# RGB_i2c_v1plusRTC_TH.net
KiCad netlist of a schematic drawn in EAGLE
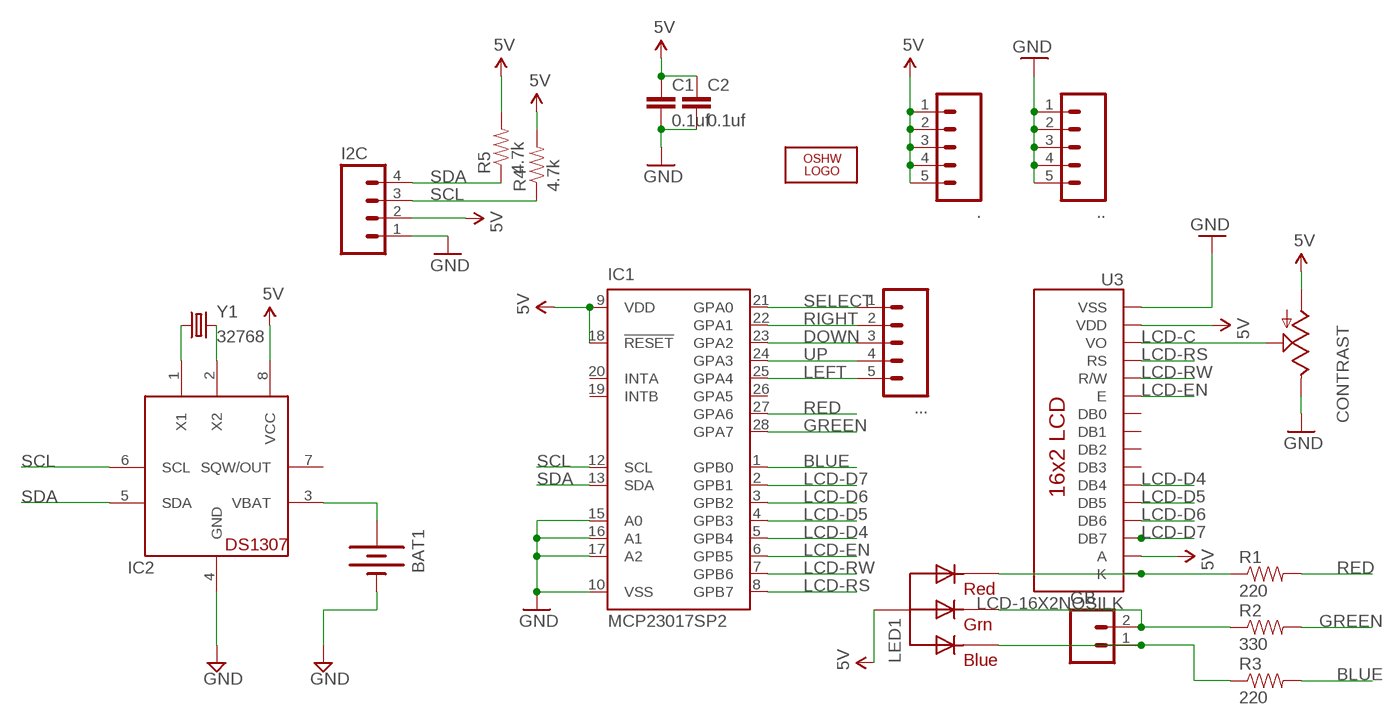
[diagram p0: schematic, sheet 1]

(export (version "E")
  (design (tool "Eeschema 10.0.6"))
  (components
    (comp (ref ".")
      (value "M05LOCK")
      (footprint "eagle-import:1X05_LOCK")
      (libsource (lib "eagle-import") (part "M05LOCK"))
    )
    (comp (ref "..")
      (value "M05LOCK")
      (footprint "eagle-import:1X05_LOCK")
      (libsource (lib "eagle-import") (part "M05LOCK"))
    )
    (comp (ref "...")
      (value "M05LOCK")
      (footprint "eagle-import:1X05_LOCK")
      (libsource (lib "eagle-import") (part "M05LOCK"))
    )
    (comp (ref "BAT1")
      (value "BATTERY12MM")
      (footprint "eagle-import:BATTCON_12MM")
      (libsource (lib "eagle-import") (part "BATTERY12MM"))
    )
    (comp (ref "C1")
      (value "0.1uf")
      (footprint "eagle-import:CAP-PTH-SMALL-KIT")
      (libsource (lib "eagle-import") (part "CAPKIT"))
    )
    (comp (ref "C2")
      (value "0.1uf")
      (footprint "eagle-import:CAP-PTH-SMALL-KIT")
      (libsource (lib "eagle-import") (part "CAPKIT"))
    )
    (comp (ref "CONTRAST")
      (value "TRIM")
      (footprint "eagle-import:6MM")
      (libsource (lib "eagle-import") (part "TRIM"))
    )
    (comp (ref "GB")
      (value "M02LOCK")
      (footprint "eagle-import:1X02_LOCK")
      (libsource (lib "eagle-import") (part "M02LOCK"))
    )
    (comp (ref "I2C")
      (value "M04LOCK")
      (footprint "eagle-import:1X04_LOCK")
      (libsource (lib "eagle-import") (part "M04LOCK"))
    )
    (comp (ref "IC1")
      (value "MCP23017SP2")
      (footprint "eagle-import:DIL28-3-ROUND")
      (libsource (lib "eagle-import") (part "MCP23017SP2"))
    )
    (comp (ref "IC2")
      (value "DS1307")
      (footprint "eagle-import:DIL08")
      (libsource (lib "eagle-import") (part "DS1307"))
    )
    (comp (ref "LED1")
      (value "RGBLED_CA-5MM")
      (footprint "eagle-import:LED5MMRGB")
      (libsource (lib "eagle-import") (part "RGBLED_CA-5MM"))
    )
    (comp (ref "LOGO2")
      (value "OSHW_LOGO_10MILX0350-NT")
      (footprint "eagle-import:OSHW_10X350_NOTEXT")
      (libsource (lib "eagle-import") (part "OSHW_LOGO_10MILX0350-NT"))
    )
    (comp (ref "R1")
      (value "220")
      (footprint "eagle-import:AXIAL-0.3")
      (libsource (lib "eagle-import") (part "RESISTORAXIAL-0.3"))
    )
    (comp (ref "R2")
      (value "330")
      (footprint "eagle-import:AXIAL-0.3")
      (libsource (lib "eagle-import") (part "RESISTORAXIAL-0.3"))
    )
    (comp (ref "R3")
      (value "220")
      (footprint "eagle-import:AXIAL-0.3")
      (libsource (lib "eagle-import") (part "RESISTORAXIAL-0.3"))
    )
    (comp (ref "R4")
      (value "4.7k")
      (footprint "eagle-import:AXIAL-0.3")
      (libsource (lib "eagle-import") (part "RESISTORAXIAL-0.3"))
    )
    (comp (ref "R5")
      (value "4.7k")
      (footprint "eagle-import:AXIAL-0.3")
      (libsource (lib "eagle-import") (part "RESISTORAXIAL-0.3"))
    )
    (comp (ref "U3")
      (value "LCD-16X2NOSILK")
      (footprint "eagle-import:LCD-16X2_NOSILK")
      (libsource (lib "eagle-import") (part "LCD-16X2NOSILK"))
    )
    (comp (ref "Y1")
      (value "32768")
      (footprint "eagle-import:TC38H")
      (libsource (lib "eagle-import") (part "CRYSTALTC38H"))
    )
  )
  (nets
    (net (code "1") (name "/BLUE") (class "Default")
      (node (ref "IC1") (pin "1") (pinfunction "GPB0_1") (pintype "bidirectional"))
      (node (ref "R3") (pin "P$2") (pinfunction "2_P$2") (pintype "passive"))
    )
    (net (code "2") (name "/DOWN") (class "Default")
      (node (ref "...") (pin "3") (pinfunction "3_3") (pintype "passive"))
      (node (ref "IC1") (pin "23") (pinfunction "GPA2_23") (pintype "bidirectional"))
    )
    (net (code "3") (name "/GREEN") (class "Default")
      (node (ref "IC1") (pin "28") (pinfunction "GPA7_28") (pintype "bidirectional"))
      (node (ref "R2") (pin "P$2") (pinfunction "2_P$2") (pintype "passive"))
    )
    (net (code "4") (name "/LCD-C") (class "Default")
      (node (ref "CONTRAST") (pin "S") (pinfunction "S_S") (pintype "passive"))
      (node (ref "U3") (pin "3") (pinfunction "VO_3") (pintype "bidirectional"))
    )
    (net (code "5") (name "/LCD-D4") (class "Default")
      (node (ref "IC1") (pin "5") (pinfunction "GPB4_5") (pintype "bidirectional"))
      (node (ref "U3") (pin "11") (pinfunction "DB4_11") (pintype "bidirectional"))
    )
    (net (code "6") (name "/LCD-D5") (class "Default")
      (node (ref "IC1") (pin "4") (pinfunction "GPB3_4") (pintype "bidirectional"))
      (node (ref "U3") (pin "12") (pinfunction "DB5_12") (pintype "bidirectional"))
    )
    (net (code "7") (name "/LCD-D6") (class "Default")
      (node (ref "IC1") (pin "3") (pinfunction "GPB2_3") (pintype "bidirectional"))
      (node (ref "U3") (pin "13") (pinfunction "DB6_13") (pintype "bidirectional"))
    )
    (net (code "8") (name "/LCD-D7") (class "Default")
      (node (ref "IC1") (pin "2") (pinfunction "GPB1_2") (pintype "bidirectional"))
      (node (ref "U3") (pin "14") (pinfunction "DB7_14") (pintype "bidirectional"))
    )
    (net (code "9") (name "/LCD-EN") (class "Default")
      (node (ref "IC1") (pin "6") (pinfunction "GPB5_6") (pintype "bidirectional"))
      (node (ref "U3") (pin "6") (pinfunction "E_6") (pintype "input"))
    )
    (net (code "10") (name "/LCD-RS") (class "Default")
      (node (ref "IC1") (pin "8") (pinfunction "GPB7_8") (pintype "bidirectional"))
      (node (ref "U3") (pin "4") (pinfunction "RS_4") (pintype "input"))
    )
    (net (code "11") (name "/LCD-RW") (class "Default")
      (node (ref "IC1") (pin "7") (pinfunction "GPB6_7") (pintype "bidirectional"))
      (node (ref "U3") (pin "5") (pinfunction "R/W_5") (pintype "input"))
    )
    (net (code "12") (name "/LEFT") (class "Default")
      (node (ref "...") (pin "5") (pinfunction "5_5") (pintype "passive"))
      (node (ref "IC1") (pin "25") (pinfunction "GPA4_25") (pintype "bidirectional"))
    )
    (net (code "13") (name "/RED") (class "Default")
      (node (ref "IC1") (pin "27") (pinfunction "GPA6_27") (pintype "bidirectional"))
      (node (ref "R1") (pin "P$2") (pinfunction "2_P$2") (pintype "passive"))
    )
    (net (code "14") (name "/RIGHT") (class "Default")
      (node (ref "...") (pin "2") (pinfunction "2_2") (pintype "passive"))
      (node (ref "IC1") (pin "22") (pinfunction "GPA1_22") (pintype "bidirectional"))
    )
    (net (code "15") (name "/SCL") (class "Default")
      (node (ref "I2C") (pin "3") (pinfunction "3_3") (pintype "passive"))
      (node (ref "IC1") (pin "12") (pinfunction "SCL_12") (pintype "input"))
      (node (ref "IC2") (pin "6") (pinfunction "SCL_6") (pintype "bidirectional"))
      (node (ref "R4") (pin "P$1") (pinfunction "1_P$1") (pintype "passive"))
    )
    (net (code "16") (name "/SDA") (class "Default")
      (node (ref "I2C") (pin "4") (pinfunction "4_4") (pintype "passive"))
      (node (ref "IC1") (pin "13") (pinfunction "SDA_13") (pintype "bidirectional"))
      (node (ref "IC2") (pin "5") (pinfunction "SDA_5") (pintype "bidirectional"))
      (node (ref "R5") (pin "P$1") (pinfunction "1_P$1") (pintype "passive"))
    )
    (net (code "17") (name "/SELECT") (class "Default")
      (node (ref "...") (pin "1") (pinfunction "1_1") (pintype "passive"))
      (node (ref "IC1") (pin "21") (pinfunction "GPA0_21") (pintype "bidirectional"))
    )
    (net (code "18") (name "/UP") (class "Default")
      (node (ref "...") (pin "4") (pinfunction "4_4") (pintype "passive"))
      (node (ref "IC1") (pin "24") (pinfunction "GPA3_24") (pintype "bidirectional"))
    )
    (net (code "19") (name "5V") (class "Default")
      (node (ref ".") (pin "1") (pinfunction "1_1") (pintype "passive"))
      (node (ref ".") (pin "2") (pinfunction "2_2") (pintype "passive"))
      (node (ref ".") (pin "3") (pinfunction "3_3") (pintype "passive"))
      (node (ref ".") (pin "4") (pinfunction "4_4") (pintype "passive"))
      (node (ref ".") (pin "5") (pinfunction "5_5") (pintype "passive"))
      (node (ref "C1") (pin "1") (pinfunction "1_1") (pintype "passive"))
      (node (ref "C2") (pin "1") (pinfunction "1_1") (pintype "passive"))
      (node (ref "CONTRAST") (pin "A") (pinfunction "A_A") (pintype "passive"))
      (node (ref "I2C") (pin "2") (pinfunction "2_2") (pintype "passive"))
      (node (ref "IC1") (pin "18") (pinfunction "~{RESET}_18") (pintype "input"))
      (node (ref "IC1") (pin "9") (pinfunction "VDD_9") (pintype "power_in"))
      (node (ref "IC2") (pin "8") (pinfunction "VCC_8") (pintype "power_in"))
      (node (ref "LED1") (pin "2") (pinfunction "VCC_2") (pintype "bidirectional"))
      (node (ref "R4") (pin "P$2") (pinfunction "2_P$2") (pintype "passive"))
      (node (ref "R5") (pin "P$2") (pinfunction "2_P$2") (pintype "passive"))
      (node (ref "U3") (pin "15") (pinfunction "A_15") (pintype "power_in"))
      (node (ref "U3") (pin "2") (pinfunction "VDD_2") (pintype "power_in"))
    )
    (net (code "20") (name "GND") (class "Default")
      (node (ref "..") (pin "1") (pinfunction "1_1") (pintype "passive"))
      (node (ref "..") (pin "2") (pinfunction "2_2") (pintype "passive"))
      (node (ref "..") (pin "3") (pinfunction "3_3") (pintype "passive"))
      (node (ref "..") (pin "4") (pinfunction "4_4") (pintype "passive"))
      (node (ref "..") (pin "5") (pinfunction "5_5") (pintype "passive"))
      (node (ref "BAT1") (pin "GND") (pinfunction "-_GND") (pintype "power_in"))
      (node (ref "C1") (pin "2") (pinfunction "2_2") (pintype "passive"))
      (node (ref "C2") (pin "2") (pinfunction "2_2") (pintype "passive"))
      (node (ref "CONTRAST") (pin "E") (pinfunction "E_E") (pintype "passive"))
      (node (ref "I2C") (pin "1") (pinfunction "1_1") (pintype "passive"))
      (node (ref "IC1") (pin "10") (pinfunction "VSS_10") (pintype "power_in"))
      (node (ref "IC1") (pin "15") (pinfunction "A0_15") (pintype "input"))
      (node (ref "IC1") (pin "16") (pinfunction "A1_16") (pintype "input"))
      (node (ref "IC1") (pin "17") (pinfunction "A2_17") (pintype "input"))
      (node (ref "IC2") (pin "4") (pinfunction "GND_4") (pintype "power_in"))
      (node (ref "U3") (pin "1") (pinfunction "VSS_1") (pintype "power_in"))
    )
    (net (code "21") (name "Net-(BAT1-+)") (class "Default")
      (node (ref "BAT1") (pin "PWR@1") (pinfunction "+_PWR@1") (pintype "power_in"))
      (node (ref "IC2") (pin "3") (pinfunction "VBAT_3") (pintype "power_in"))
    )
    (net (code "22") (name "Net-(IC2-X1)") (class "Default")
      (node (ref "IC2") (pin "1") (pinfunction "X1_1") (pintype "passive"))
      (node (ref "Y1") (pin "1") (pinfunction "1_1") (pintype "passive"))
    )
    (net (code "23") (name "Net-(IC2-X2)") (class "Default")
      (node (ref "IC2") (pin "2") (pinfunction "X2_2") (pintype "passive"))
      (node (ref "Y1") (pin "2") (pinfunction "2_2") (pintype "passive"))
    )
    (net (code "24") (name "Net-(LED1-BLUE)") (class "Default")
      (node (ref "GB") (pin "1") (pinfunction "1_1") (pintype "passive"))
      (node (ref "LED1") (pin "4") (pinfunction "BLUE_4") (pintype "bidirectional"))
      (node (ref "R3") (pin "P$1") (pinfunction "1_P$1") (pintype "passive"))
    )
    (net (code "25") (name "Net-(LED1-GREEN)") (class "Default")
      (node (ref "GB") (pin "2") (pinfunction "2_2") (pintype "passive"))
      (node (ref "LED1") (pin "3") (pinfunction "GREEN_3") (pintype "bidirectional"))
      (node (ref "R2") (pin "P$1") (pinfunction "1_P$1") (pintype "passive"))
    )
    (net (code "26") (name "Net-(LED1-RED)") (class "Default")
      (node (ref "LED1") (pin "1") (pinfunction "RED_1") (pintype "bidirectional"))
      (node (ref "R1") (pin "P$1") (pinfunction "1_P$1") (pintype "passive"))
      (node (ref "U3") (pin "16") (pinfunction "K_16") (pintype "power_in"))
    )
    (net (code "27") (name "unconnected-(IC1-GPA5-Pad26)") (class "Default")
      (node (ref "IC1") (pin "26") (pinfunction "GPA5_26") (pintype "bidirectional"))
    )
    (net (code "28") (name "unconnected-(IC1-INTA-Pad20)") (class "Default")
      (node (ref "IC1") (pin "20") (pinfunction "INTA_20") (pintype "output"))
    )
    (net (code "29") (name "unconnected-(IC1-INTB-Pad19)") (class "Default")
      (node (ref "IC1") (pin "19") (pinfunction "INTB_19") (pintype "output"))
    )
    (net (code "30") (name "unconnected-(IC2-SQW{slash}OUT-Pad7)") (class "Default")
      (node (ref "IC2") (pin "7") (pinfunction "SQW/OUT_7") (pintype "bidirectional"))
    )
    (net (code "31") (name "unconnected-(U3-DB0-Pad7)") (class "Default")
      (node (ref "U3") (pin "7") (pinfunction "DB0_7") (pintype "bidirectional"))
    )
    (net (code "32") (name "unconnected-(U3-DB1-Pad8)") (class "Default")
      (node (ref "U3") (pin "8") (pinfunction "DB1_8") (pintype "bidirectional"))
    )
    (net (code "33") (name "unconnected-(U3-DB2-Pad9)") (class "Default")
      (node (ref "U3") (pin "9") (pinfunction "DB2_9") (pintype "bidirectional"))
    )
    (net (code "34") (name "unconnected-(U3-DB3-Pad10)") (class "Default")
      (node (ref "U3") (pin "10") (pinfunction "DB3_10") (pintype "bidirectional"))
    )
  )
)
